# IDD_measurement.net
KiCad netlist of a schematic drawn in Altium Designer
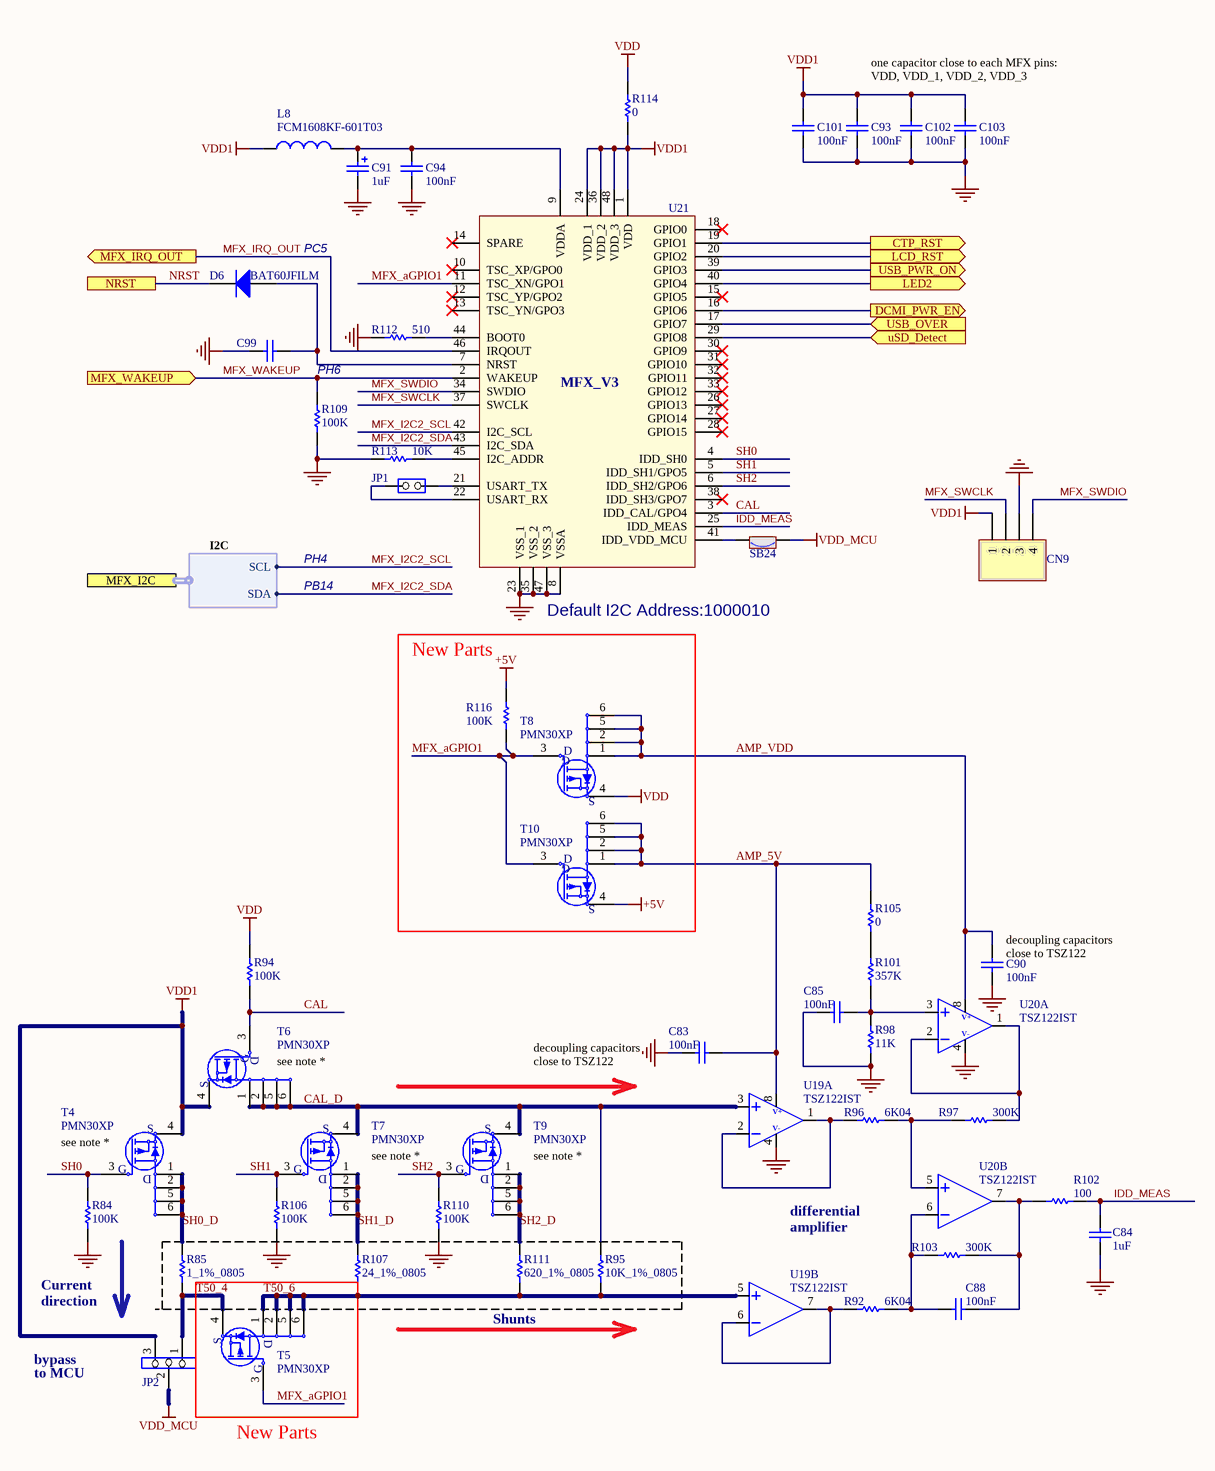
[diagram p0: IDD_measurement.SchDoc]

(export (version "E")
  (design (tool "Eeschema 10.0.6"))
  (components
    (comp (ref "C83")
      (value "100nF")
      (footprint "0603C")
      (description "Capacitor,100nF,10%,16V,X7R,0603,YAGEO")
      (fields (field (name "Comment") "CC0603KRX7R7BB104") (field (name "PUBLISHER") "Altium Limited"))
      (libsource (lib "Miscellaneous Devices") (part "Cap"))
    )
    (comp (ref "C84")
      (value "1uF")
      (footprint "0603C")
      (description "Capacitor,1uF,0603,16V,10%,X5R,YAGEO")
      (fields (field (name "Comment") "CC0603KRX5R7BB105") (field (name "PUBLISHER") "Altium Limited"))
      (libsource (lib "Miscellaneous Devices") (part "Cap"))
    )
    (comp (ref "C85")
      (value "100nF")
      (footprint "0603C")
      (description "Capacitor,100nF,10%,16V,X7R,0603,YAGEO")
      (fields (field (name "Comment") "CC0603KRX7R7BB104") (field (name "PUBLISHER") "Altium Limited"))
      (libsource (lib "Miscellaneous Devices") (part "Cap"))
    )
    (comp (ref "C88")
      (value "100nF")
      (footprint "0603C")
      (description "Capacitor,100nF,10%,16V,X7R,0603,YAGEO")
      (fields (field (name "Comment") "CC0603KRX7R7BB104") (field (name "PUBLISHER") "Altium Limited"))
      (libsource (lib "Miscellaneous Devices") (part "Cap"))
    )
    (comp (ref "C90")
      (value "100nF")
      (footprint "0603C")
      (description "Capacitor,100nF,10%,16V,X7R,0603,YAGEO")
      (fields (field (name "Comment") "CC0603KRX7R7BB104") (field (name "PUBLISHER") "Altium Limited"))
      (libsource (lib "Miscellaneous Devices") (part "Cap"))
    )
    (comp (ref "C91")
      (value "1uF")
      (footprint "TAN-A")
      (description "Tan Capacitor,1uF,10%,16V,Tan-A,TAJA105K016R")
      (fields (field (name "Comment") "TAJA105K016R") (field (name "PUBLISHER") "Altium Limited"))
      (libsource (lib "Miscellaneous Devices") (part "Cap Pol1"))
    )
    (comp (ref "C93")
      (value "100nF")
      (footprint "0603C")
      (description "Capacitor,100nF,10%,16V,X7R,0603,YAGEO")
      (fields (field (name "Comment") "CC0603KRX7R7BB104") (field (name "PUBLISHER") "Altium Limited"))
      (libsource (lib "Miscellaneous Devices") (part "Cap"))
    )
    (comp (ref "C94")
      (value "100nF")
      (footprint "0603C")
      (description "Capacitor,100nF,10%,16V,X7R,0603,YAGEO")
      (fields (field (name "Comment") "CC0603KRX7R7BB104") (field (name "PUBLISHER") "Altium Limited"))
      (libsource (lib "Miscellaneous Devices") (part "Cap"))
    )
    (comp (ref "C99")
      (value "~")
      (footprint "0603C")
      (description "Capacitor,100nF,10%,16V,X7R,0603,YAGEO")
      (fields (field (name "PUBLISHER") "Altium Limited"))
      (libsource (lib "Miscellaneous Devices") (part "Cap"))
    )
    (comp (ref "C101")
      (value "100nF")
      (footprint "0603C")
      (description "Capacitor,100nF,10%,16V,X7R,0603,YAGEO")
      (fields (field (name "Comment") "CC0603KRX7R7BB104") (field (name "PUBLISHER") "Altium Limited"))
      (libsource (lib "Miscellaneous Devices") (part "Cap"))
    )
    (comp (ref "C102")
      (value "100nF")
      (footprint "0603C")
      (description "Capacitor,100nF,10%,16V,X7R,0603,YAGEO")
      (fields (field (name "Comment") "CC0603KRX7R7BB104") (field (name "PUBLISHER") "Altium Limited"))
      (libsource (lib "Miscellaneous Devices") (part "Cap"))
    )
    (comp (ref "C103")
      (value "100nF")
      (footprint "0603C")
      (description "Capacitor,100nF,10%,16V,X7R,0603,YAGEO")
      (fields (field (name "Comment") "CC0603KRX7R7BB104") (field (name "PUBLISHER") "Altium Limited"))
      (libsource (lib "Miscellaneous Devices") (part "Cap"))
    )
    (comp (ref "CN9")
      (value "~")
      (footprint "HDR_1X4_2R54")
      (description "Header, 4-Pin")
      (fields (field (name "PUBLISHER") "Altium Limited"))
      (libsource (lib "MCD_TOOLS_CONNECTOR") (part "Header 4"))
    )
    (comp (ref "D6")
      (value "BAT60JFILM")
      (footprint "SOD-323")
      (fields (field (name "PROVIDED") "STM"))
      (libsource (lib "MCD_TOOLS") (part "BAT60JFILM"))
    )
    (comp (ref "JP1")
      (value "~")
      (footprint "SIP2")
      (description "2 PIN Jumper")
      (libsource (lib "*") (part "JP2"))
    )
    (comp (ref "JP2")
      (value "3 PIN Jumper")
      (footprint "SIP3")
      (description "Jumper 3 pins")
      (libsource (lib "MCD_TOOLS") (part "Jumper3"))
    )
    (comp (ref "L8")
      (value "FCM1608KF-601T03")
      (footprint "0603L")
      (description "Bead,600R,350mA,0603,FCM1608KF-601T03,Tai-tech")
      (libsource (lib "MCD_TOOLS") (part "BEAD_600R_350MA_0603"))
    )
    (comp (ref "R84")
      (value "100K")
      (footprint "0603R")
      (description "Resistor,100K,0603,1%,YAGEO")
      (fields (field (name "Comment") "RC0603FR-07100KL") (field (name "PUBLISHER") "Altium Limited"))
      (libsource (lib "Miscellaneous Devices") (part "res1"))
    )
    (comp (ref "R85")
      (value "1_1%_0805")
      (footprint "0805R")
      (description "Resistor,1,0805,1%,YAGEO")
      (libsource (lib "MCD_TOOLS") (part "Res_1_1%_0805"))
    )
    (comp (ref "R92")
      (value "6K04")
      (footprint "0603R")
      (description "Resistor,6.04K,0603,1%,YAGEO")
      (fields (field (name "Comment") "RC0603FR-076K04L") (field (name "PUBLISHER") "Altium Limited"))
      (libsource (lib "Miscellaneous Devices") (part "res1"))
    )
    (comp (ref "R94")
      (value "100K")
      (footprint "0603R")
      (description "Resistor,100K,0603,1%,YAGEO")
      (fields (field (name "Comment") "RC0603FR-07100KL") (field (name "PUBLISHER") "Altium Limited"))
      (libsource (lib "Miscellaneous Devices") (part "res1"))
    )
    (comp (ref "R95")
      (value "10K_1%_0805")
      (footprint "0805R")
      (description "Resistor,10K,0805,1%,YAGEO")
      (libsource (lib "MCD_TOOLS") (part "Res_10K_1%_0805"))
    )
    (comp (ref "R96")
      (value "6K04")
      (footprint "0603R")
      (description "Resistor,6.04K,0603,1%,YAGEO")
      (fields (field (name "Comment") "RC0603FR-076K04L") (field (name "PUBLISHER") "Altium Limited"))
      (libsource (lib "Miscellaneous Devices") (part "res1"))
    )
    (comp (ref "R97")
      (value "300K")
      (footprint "0603R")
      (description "Resistor,300K,0603,1%,YAGEO")
      (fields (field (name "Comment") "RC0603FR-07300KL") (field (name "PUBLISHER") "Altium Limited"))
      (libsource (lib "Miscellaneous Devices") (part "res1"))
    )
    (comp (ref "R98")
      (value "11K")
      (footprint "0603R")
      (description "Resistor,11K,0603,1%,YAGEO")
      (fields (field (name "Comment") "RC0603FR-0711KL") (field (name "PUBLISHER") "Altium Limited"))
      (libsource (lib "Miscellaneous Devices") (part "res1"))
    )
    (comp (ref "R101")
      (value "357K")
      (footprint "0603R")
      (description "Resistor,357K,0603,1%,YAGEO")
      (fields (field (name "Comment") "RC0603FR-07357KL") (field (name "PUBLISHER") "Altium Limited"))
      (libsource (lib "Miscellaneous Devices") (part "res1"))
    )
    (comp (ref "R102")
      (value "100")
      (footprint "0603R")
      (description "Resistor, 100 ,0603,1%,YAGEO")
      (fields (field (name "Comment") "RC0603JR-07100RL") (field (name "PUBLISHER") "Altium Limited"))
      (libsource (lib "Miscellaneous Devices") (part "res1"))
    )
    (comp (ref "R103")
      (value "300K")
      (footprint "0603R")
      (description "Resistor,300K,0603,1%,YAGEO")
      (fields (field (name "Comment") "RC0603FR-07300KL") (field (name "PUBLISHER") "Altium Limited"))
      (libsource (lib "Miscellaneous Devices") (part "res1"))
    )
    (comp (ref "R105")
      (value "0")
      (footprint "0603R")
      (description "Resistor, 0 ,0603,1%,YAGEO")
      (fields (field (name "Comment") "RC0603JR-070RL") (field (name "PUBLISHER") "Altium Limited"))
      (libsource (lib "Miscellaneous Devices") (part "res1"))
    )
    (comp (ref "R106")
      (value "100K")
      (footprint "0603R")
      (description "Resistor,100K,0603,1%,YAGEO")
      (fields (field (name "Comment") "RC0603FR-07100KL") (field (name "PUBLISHER") "Altium Limited"))
      (libsource (lib "Miscellaneous Devices") (part "res1"))
    )
    (comp (ref "R107")
      (value "24_1%_0805")
      (footprint "0805R")
      (description "Resistor,24,0805,1%,YAGEO")
      (libsource (lib "MCD_TOOLS") (part "Res_24_1%_0805"))
    )
    (comp (ref "R109")
      (value "100K")
      (footprint "0603R")
      (description "Resistor,100K,0603,1%,YAGEO")
      (fields (field (name "Comment") "RC0603FR-07100KL") (field (name "PUBLISHER") "Altium Limited"))
      (libsource (lib "Miscellaneous Devices") (part "res1"))
    )
    (comp (ref "R110")
      (value "100K")
      (footprint "0603R")
      (description "Resistor,100K,0603,1%,YAGEO")
      (fields (field (name "Comment") "RC0603FR-07100KL") (field (name "PUBLISHER") "Altium Limited"))
      (libsource (lib "Miscellaneous Devices") (part "res1"))
    )
    (comp (ref "R111")
      (value "620_1%_0805")
      (footprint "0805R")
      (description "Resistor,620,0805,1%,YAGEO")
      (libsource (lib "MCD_TOOLS") (part "Res_620_1%_0805"))
    )
    (comp (ref "R112")
      (value "510")
      (footprint "0603R")
      (description "Resistor,510R,0603,1%,YAGEO")
      (fields (field (name "Comment") "RC0603FR-07510RL") (field (name "PUBLISHER") "Altium Limited"))
      (libsource (lib "Miscellaneous Devices") (part "res1"))
    )
    (comp (ref "R113")
      (value "10K")
      (footprint "0603R")
      (description "Resistor,10K,0603,1%,YAGEO")
      (fields (field (name "Comment") "RC0603FR-0710KL") (field (name "PUBLISHER") "Altium Limited"))
      (libsource (lib "Miscellaneous Devices") (part "res1"))
    )
    (comp (ref "R114")
      (value "0")
      (footprint "0603R")
      (description "Resistor, 0 ,0603,1%,YAGEO")
      (fields (field (name "Comment") "RC0603JR-070RL") (field (name "PUBLISHER") "Altium Limited"))
      (libsource (lib "Miscellaneous Devices") (part "res1"))
    )
    (comp (ref "R116")
      (value "100K")
      (footprint "0603R")
      (description "Resistor,100K,0603,1%,YAGEO")
      (fields (field (name "Comment") "RC0603FR-07100KL") (field (name "PUBLISHER") "Altium Limited"))
      (libsource (lib "Miscellaneous Devices") (part "res1"))
    )
    (comp (ref "SB24")
      (value "Solder Bridge ON")
      (footprint "SB_0603")
      (libsource (lib "MCD_TOOLS") (part "SB_ON"))
    )
    (comp (ref "T4")
      (value "PMN30XP")
      (footprint "MOS_SOT23-6L")
      (description "20 V, P-channel Trench MOSFET")
      (fields (field (name "INTERNAL_PART_NUMBER") "MCD-01926") (field (name "MANUFACTURER") "NEXPERIA"))
      (libsource (lib "MCD_PARTS_database") (part "PMN30XP"))
    )
    (comp (ref "T5")
      (value "PMN30XP")
      (footprint "MOS_SOT23-6L")
      (description "20 V, P-channel Trench MOSFET")
      (fields (field (name "INTERNAL_PART_NUMBER") "MCD-01926") (field (name "MANUFACTURER") "NEXPERIA"))
      (libsource (lib "MCD_PARTS_database") (part "PMN30XP"))
    )
    (comp (ref "T6")
      (value "PMN30XP")
      (footprint "MOS_SOT23-6L")
      (description "20 V, P-channel Trench MOSFET")
      (fields (field (name "INTERNAL_PART_NUMBER") "MCD-01926") (field (name "MANUFACTURER") "NEXPERIA"))
      (libsource (lib "MCD_PARTS_database") (part "PMN30XP"))
    )
    (comp (ref "T7")
      (value "PMN30XP")
      (footprint "MOS_SOT23-6L")
      (description "20 V, P-channel Trench MOSFET")
      (fields (field (name "INTERNAL_PART_NUMBER") "MCD-01926") (field (name "MANUFACTURER") "NEXPERIA"))
      (libsource (lib "MCD_PARTS_database") (part "PMN30XP"))
    )
    (comp (ref "T8")
      (value "PMN30XP")
      (footprint "MOS_SOT23-6L")
      (description "20 V, P-channel Trench MOSFET")
      (fields (field (name "INTERNAL_PART_NUMBER") "MCD-01926") (field (name "MANUFACTURER") "NEXPERIA"))
      (libsource (lib "MCD_PARTS_database") (part "PMN30XP"))
    )
    (comp (ref "T9")
      (value "PMN30XP")
      (footprint "MOS_SOT23-6L")
      (description "20 V, P-channel Trench MOSFET")
      (fields (field (name "INTERNAL_PART_NUMBER") "MCD-01926") (field (name "MANUFACTURER") "NEXPERIA"))
      (libsource (lib "MCD_PARTS_database") (part "PMN30XP"))
    )
    (comp (ref "T10")
      (value "PMN30XP")
      (footprint "MOS_SOT23-6L")
      (description "20 V, P-channel Trench MOSFET")
      (fields (field (name "INTERNAL_PART_NUMBER") "MCD-01926") (field (name "MANUFACTURER") "NEXPERIA"))
      (libsource (lib "MCD_PARTS_database") (part "PMN30XP"))
    )
    (comp (ref "U19")
      (value "TSZ122IST")
      (footprint "miniSO8")
      (description "Very high accuracy (5 礦) zero drift 5 V dual OpAmp")
      (libsource (lib "MCD_TOOLS") (part "TSZ122IST"))
    )
    (comp (ref "U20")
      (value "TSZ122IST")
      (footprint "miniSO8")
      (description "Very high accuracy (5 礦) zero drift 5 V dual OpAmp")
      (libsource (lib "MCD_TOOLS") (part "TSZ122IST"))
    )
    (comp (ref "U21")
      (value "STM32L152CCT6")
      (footprint "LQFP48_0R5_9X9")
      (description "Multifunction expander")
      (libsource (lib "MB1167") (part "MFX"))
    )
  )
  (nets
    (net (code "2") (name "+5V") (class "Default")
      (node (ref "R116") (pin "2") (pinfunction "2_2") (pintype "passive"))
      (node (ref "T10") (pin "4") (pinfunction "S_4") (pintype "passive"))
    )
    (net (code "3") (name "/AMP_5V") (class "Default")
      (node (ref "C83") (pin "2") (pinfunction "2_2") (pintype "passive"))
      (node (ref "R105") (pin "2") (pinfunction "2_2") (pintype "passive"))
      (node (ref "T10") (pin "1") (pinfunction "S_1") (pintype "passive"))
      (node (ref "T10") (pin "2") (pinfunction "S_2") (pintype "passive"))
      (node (ref "T10") (pin "5") (pinfunction "D_5") (pintype "passive"))
      (node (ref "T10") (pin "6") (pinfunction "D_6") (pintype "passive"))
      (node (ref "U19") (pin "8") (pintype "passive"))
    )
    (net (code "4") (name "/AMP_VDD") (class "Default")
      (node (ref "C90") (pin "1") (pinfunction "1_1") (pintype "passive"))
      (node (ref "T8") (pin "1") (pinfunction "S_1") (pintype "passive"))
      (node (ref "T8") (pin "2") (pinfunction "S_2") (pintype "passive"))
      (node (ref "T8") (pin "5") (pinfunction "D_5") (pintype "passive"))
      (node (ref "T8") (pin "6") (pinfunction "D_6") (pintype "passive"))
      (node (ref "U20") (pin "8") (pintype "passive"))
    )
    (net (code "5") (name "/CAL") (class "Default")
      (node (ref "R94") (pin "1") (pinfunction "1_1") (pintype "passive"))
      (node (ref "T6") (pin "3") (pinfunction "G_3") (pintype "passive"))
      (node (ref "U21") (pin "3") (pinfunction "IDD_CAL/GPO4_3") (pintype "passive"))
    )
    (net (code "6") (name "/CAL_D") (class "Default")
      (node (ref "R95") (pin "2") (pinfunction "2_2") (pintype "passive"))
      (node (ref "T6") (pin "1") (pinfunction "S_1") (pintype "passive"))
      (node (ref "T6") (pin "2") (pinfunction "S_2") (pintype "passive"))
      (node (ref "T6") (pin "5") (pinfunction "D_5") (pintype "passive"))
      (node (ref "T6") (pin "6") (pinfunction "D_6") (pintype "passive"))
      (node (ref "T7") (pin "4") (pinfunction "S_4") (pintype "passive"))
      (node (ref "T9") (pin "4") (pinfunction "S_4") (pintype "passive"))
      (node (ref "U19") (pin "3") (pintype "passive"))
    )
    (net (code "7") (name "/CTP_RST") (class "Default")
      (node (ref "U21") (pin "19") (pinfunction "GPIO1_19") (pintype "passive"))
    )
    (net (code "8") (name "/DCMI_PWR_EN") (class "Default")
      (node (ref "U21") (pin "16") (pinfunction "GPIO6_16") (pintype "passive"))
    )
    (net (code "9") (name "/IDD_MEAS") (class "Default")
      (node (ref "C84") (pin "1") (pinfunction "1_1") (pintype "passive"))
      (node (ref "R102") (pin "1") (pinfunction "1_1") (pintype "passive"))
      (node (ref "U21") (pin "25") (pinfunction "IDD_MEAS_25") (pintype "passive"))
    )
    (net (code "10") (name "/LCD_RST") (class "Default")
      (node (ref "U21") (pin "20") (pinfunction "GPIO2_20") (pintype "passive"))
    )
    (net (code "11") (name "/LED2") (class "Default")
      (node (ref "U21") (pin "40") (pinfunction "GPIO4_40") (pintype "passive"))
    )
    (net (code "12") (name "/MFX_I2C2_SCL") (class "Default")
      (node (ref "U21") (pin "42") (pinfunction "I2C_SCL_42") (pintype "passive"))
    )
    (net (code "13") (name "/MFX_I2C2_SDA") (class "Default")
      (node (ref "U21") (pin "43") (pinfunction "I2C_SDA_43") (pintype "passive"))
    )
    (net (code "14") (name "/MFX_IRQ_OUT") (class "Default")
      (node (ref "U21") (pin "46") (pinfunction "IRQOUT_46") (pintype "passive"))
    )
    (net (code "15") (name "/MFX_SWCLK") (class "Default")
      (node (ref "CN9") (pin "2") (pinfunction "2_2") (pintype "passive"))
      (node (ref "U21") (pin "37") (pinfunction "SWCLK_37") (pintype "passive"))
    )
    (net (code "16") (name "/MFX_SWDIO") (class "Default")
      (node (ref "CN9") (pin "4") (pinfunction "4_4") (pintype "passive"))
      (node (ref "U21") (pin "34") (pinfunction "SWDIO_34") (pintype "passive"))
    )
    (net (code "17") (name "/MFX_WAKEUP") (class "Default")
      (node (ref "R109") (pin "2") (pinfunction "2_2") (pintype "passive"))
      (node (ref "U21") (pin "2") (pinfunction "WAKEUP_2") (pintype "passive"))
    )
    (net (code "18") (name "/MFX_aGPIO1") (class "Default")
      (node (ref "R116") (pin "1") (pinfunction "1_1") (pintype "passive"))
      (node (ref "T10") (pin "3") (pinfunction "G_3") (pintype "passive"))
      (node (ref "T5") (pin "3") (pinfunction "G_3") (pintype "passive"))
      (node (ref "T8") (pin "3") (pinfunction "G_3") (pintype "passive"))
      (node (ref "U21") (pin "11") (pinfunction "TSC_XN/GPO1_11") (pintype "passive"))
    )
    (net (code "19") (name "/NRST") (class "Default")
      (node (ref "D6") (pin "2") (pinfunction "K_2") (pintype "passive"))
    )
    (net (code "20") (name "/SH0") (class "Default")
      (node (ref "R84") (pin "2") (pinfunction "2_2") (pintype "passive"))
      (node (ref "T4") (pin "3") (pinfunction "G_3") (pintype "passive"))
      (node (ref "U21") (pin "4") (pinfunction "IDD_SH0_4") (pintype "passive"))
    )
    (net (code "21") (name "/SH0_D") (class "Default")
      (node (ref "R85") (pin "2") (pinfunction "2_2") (pintype "passive"))
      (node (ref "T4") (pin "1") (pinfunction "S_1") (pintype "passive"))
      (node (ref "T4") (pin "2") (pinfunction "S_2") (pintype "passive"))
      (node (ref "T4") (pin "5") (pinfunction "D_5") (pintype "passive"))
      (node (ref "T4") (pin "6") (pinfunction "D_6") (pintype "passive"))
    )
    (net (code "22") (name "/SH1") (class "Default")
      (node (ref "R106") (pin "2") (pinfunction "2_2") (pintype "passive"))
      (node (ref "T7") (pin "3") (pinfunction "G_3") (pintype "passive"))
      (node (ref "U21") (pin "5") (pinfunction "IDD_SH1/GPO5_5") (pintype "passive"))
    )
    (net (code "23") (name "/SH1_D") (class "Default")
      (node (ref "R107") (pin "2") (pinfunction "2_2") (pintype "passive"))
      (node (ref "T7") (pin "1") (pinfunction "S_1") (pintype "passive"))
      (node (ref "T7") (pin "2") (pinfunction "S_2") (pintype "passive"))
      (node (ref "T7") (pin "5") (pinfunction "D_5") (pintype "passive"))
      (node (ref "T7") (pin "6") (pinfunction "D_6") (pintype "passive"))
    )
    (net (code "24") (name "/SH2") (class "Default")
      (node (ref "R110") (pin "2") (pinfunction "2_2") (pintype "passive"))
      (node (ref "T9") (pin "3") (pinfunction "G_3") (pintype "passive"))
      (node (ref "U21") (pin "6") (pinfunction "IDD_SH2/GPO6_6") (pintype "passive"))
    )
    (net (code "25") (name "/SH2_D") (class "Default")
      (node (ref "R111") (pin "2") (pinfunction "2_2") (pintype "passive"))
      (node (ref "T9") (pin "1") (pinfunction "S_1") (pintype "passive"))
      (node (ref "T9") (pin "2") (pinfunction "S_2") (pintype "passive"))
      (node (ref "T9") (pin "5") (pinfunction "D_5") (pintype "passive"))
      (node (ref "T9") (pin "6") (pinfunction "D_6") (pintype "passive"))
    )
    (net (code "26") (name "/T50_4") (class "Default")
      (node (ref "JP2") (pin "1") (pintype "passive"))
      (node (ref "R85") (pin "1") (pinfunction "1_1") (pintype "passive"))
      (node (ref "T5") (pin "4") (pinfunction "S_4") (pintype "passive"))
    )
    (net (code "27") (name "/T50_6") (class "Default")
      (node (ref "R107") (pin "1") (pinfunction "1_1") (pintype "passive"))
      (node (ref "R111") (pin "1") (pinfunction "1_1") (pintype "passive"))
      (node (ref "R95") (pin "1") (pinfunction "1_1") (pintype "passive"))
      (node (ref "T5") (pin "1") (pinfunction "S_1") (pintype "passive"))
      (node (ref "T5") (pin "2") (pinfunction "S_2") (pintype "passive"))
      (node (ref "T5") (pin "5") (pinfunction "D_5") (pintype "passive"))
      (node (ref "T5") (pin "6") (pinfunction "D_6") (pintype "passive"))
      (node (ref "U19") (pin "5") (pintype "passive"))
    )
    (net (code "28") (name "/USB_OVER") (class "Default")
      (node (ref "U21") (pin "17") (pinfunction "GPIO7_17") (pintype "passive"))
    )
    (net (code "29") (name "/USB_PWR_ON") (class "Default")
      (node (ref "U21") (pin "39") (pinfunction "GPIO3_39") (pintype "passive"))
    )
    (net (code "30") (name "/uSD_Detect") (class "Default")
      (node (ref "U21") (pin "29") (pinfunction "GPIO8_29") (pintype "passive"))
    )
    (net (code "32") (name "GND") (class "Default")
      (node (ref "C101") (pin "2") (pinfunction "2_2") (pintype "passive"))
      (node (ref "C102") (pin "2") (pinfunction "2_2") (pintype "passive"))
      (node (ref "C103") (pin "2") (pinfunction "2_2") (pintype "passive"))
      (node (ref "C83") (pin "1") (pinfunction "1_1") (pintype "passive"))
      (node (ref "C84") (pin "2") (pinfunction "2_2") (pintype "passive"))
      (node (ref "C85") (pin "1") (pinfunction "1_1") (pintype "passive"))
      (node (ref "C90") (pin "2") (pinfunction "2_2") (pintype "passive"))
      (node (ref "C91") (pin "2") (pinfunction "2_2") (pintype "passive"))
      (node (ref "C93") (pin "2") (pinfunction "2_2") (pintype "passive"))
      (node (ref "C94") (pin "2") (pinfunction "2_2") (pintype "passive"))
      (node (ref "C99") (pin "1") (pinfunction "1_1") (pintype "passive"))
      (node (ref "CN9") (pin "3") (pinfunction "3_3") (pintype "passive"))
      (node (ref "R106") (pin "1") (pinfunction "1_1") (pintype "passive"))
      (node (ref "R109") (pin "1") (pinfunction "1_1") (pintype "passive"))
      (node (ref "R110") (pin "1") (pinfunction "1_1") (pintype "passive"))
      (node (ref "R112") (pin "2") (pinfunction "2_2") (pintype "passive"))
      (node (ref "R113") (pin "2") (pinfunction "2_2") (pintype "passive"))
      (node (ref "R84") (pin "1") (pinfunction "1_1") (pintype "passive"))
      (node (ref "R98") (pin "2") (pinfunction "2_2") (pintype "passive"))
      (node (ref "U19") (pin "4") (pintype "passive"))
      (node (ref "U20") (pin "4") (pintype "passive"))
      (node (ref "U21") (pin "23") (pinfunction "VSS_1_23") (pintype "passive"))
      (node (ref "U21") (pin "35") (pinfunction "VSS_2_35") (pintype "passive"))
      (node (ref "U21") (pin "47") (pinfunction "VSS_3_47") (pintype "passive"))
      (node (ref "U21") (pin "8") (pinfunction "VSSA_8") (pintype "passive"))
    )
    (net (code "33") (name "Net-(C85-Pad2)") (class "Default")
      (node (ref "C85") (pin "2") (pinfunction "2_2") (pintype "passive"))
      (node (ref "R101") (pin "2") (pinfunction "2_2") (pintype "passive"))
      (node (ref "R98") (pin "1") (pinfunction "1_1") (pintype "passive"))
      (node (ref "U20") (pin "3") (pintype "passive"))
    )
    (net (code "34") (name "Net-(C88-Pad1)") (class "Default")
      (node (ref "C88") (pin "1") (pinfunction "1_1") (pintype "passive"))
      (node (ref "R103") (pin "1") (pinfunction "1_1") (pintype "passive"))
      (node (ref "R92") (pin "1") (pinfunction "1_1") (pintype "passive"))
      (node (ref "U20") (pin "6") (pintype "passive"))
    )
    (net (code "35") (name "Net-(C88-Pad2)") (class "Default")
      (node (ref "C88") (pin "2") (pinfunction "2_2") (pintype "passive"))
      (node (ref "R102") (pin "2") (pinfunction "2_2") (pintype "passive"))
      (node (ref "R103") (pin "2") (pinfunction "2_2") (pintype "passive"))
      (node (ref "U20") (pin "7") (pintype "passive"))
    )
    (net (code "36") (name "Net-(D6-A)") (class "Default")
      (node (ref "C99") (pin "2") (pinfunction "2_2") (pintype "passive"))
      (node (ref "D6") (pin "1") (pinfunction "A_1") (pintype "passive"))
      (node (ref "U21") (pin "7") (pinfunction "NRST_7") (pintype "passive"))
    )
    (net (code "37") (name "Net-(JP1-COMMON)") (class "Default")
      (node (ref "JP1") (pin "1") (pinfunction "COMMON_1") (pintype "passive"))
      (node (ref "U21") (pin "22") (pinfunction "USART_RX_22") (pintype "passive"))
    )
    (net (code "38") (name "Net-(JP1-NO)") (class "Default")
      (node (ref "JP1") (pin "2") (pinfunction "NO_2") (pintype "passive"))
      (node (ref "U21") (pin "21") (pinfunction "USART_TX_21") (pintype "passive"))
    )
    (net (code "39") (name "Net-(R92-Pad2)") (class "Default")
      (node (ref "R92") (pin "2") (pinfunction "2_2") (pintype "passive"))
      (node (ref "U19") (pin "6") (pintype "passive"))
      (node (ref "U19") (pin "7") (pintype "passive"))
    )
    (net (code "40") (name "Net-(R96-Pad1)") (class "Default")
      (node (ref "R96") (pin "1") (pinfunction "1_1") (pintype "passive"))
      (node (ref "R97") (pin "1") (pinfunction "1_1") (pintype "passive"))
      (node (ref "U20") (pin "5") (pintype "passive"))
    )
    (net (code "41") (name "Net-(R96-Pad2)") (class "Default")
      (node (ref "R96") (pin "2") (pinfunction "2_2") (pintype "passive"))
      (node (ref "U19") (pin "1") (pintype "passive"))
      (node (ref "U19") (pin "2") (pintype "passive"))
    )
    (net (code "42") (name "Net-(R97-Pad2)") (class "Default")
      (node (ref "R97") (pin "2") (pinfunction "2_2") (pintype "passive"))
      (node (ref "U20") (pin "1") (pintype "passive"))
      (node (ref "U20") (pin "2") (pintype "passive"))
    )
    (net (code "43") (name "Net-(R101-Pad1)") (class "Default")
      (node (ref "R101") (pin "1") (pinfunction "1_1") (pintype "passive"))
      (node (ref "R105") (pin "1") (pinfunction "1_1") (pintype "passive"))
    )
    (net (code "44") (name "Net-(U21-BOOT0)") (class "Default")
      (node (ref "R112") (pin "1") (pinfunction "1_1") (pintype "passive"))
      (node (ref "U21") (pin "44") (pinfunction "BOOT0_44") (pintype "passive"))
    )
    (net (code "45") (name "Net-(U21-I2C_ADDR)") (class "Default")
      (node (ref "R113") (pin "1") (pinfunction "1_1") (pintype "passive"))
      (node (ref "U21") (pin "45") (pinfunction "I2C_ADDR_45") (pintype "passive"))
    )
    (net (code "46") (name "Net-(U21-IDD_VDD_MCU)") (class "Default")
      (node (ref "SB24") (pin "2") (pinfunction "2_2") (pintype "passive"))
      (node (ref "U21") (pin "41") (pinfunction "IDD_VDD_MCU_41") (pintype "passive"))
    )
    (net (code "47") (name "Net-(U21-VDDA)") (class "Default")
      (node (ref "C91") (pin "1") (pinfunction "1_1") (pintype "passive"))
      (node (ref "C94") (pin "1") (pinfunction "1_1") (pintype "passive"))
      (node (ref "L8") (pin "2") (pinfunction "2_2") (pintype "passive"))
      (node (ref "U21") (pin "9") (pinfunction "VDDA_9") (pintype "passive"))
    )
    (net (code "48") (name "VDD") (class "Default")
      (node (ref "R114") (pin "1") (pinfunction "1_1") (pintype "passive"))
      (node (ref "R94") (pin "2") (pinfunction "2_2") (pintype "passive"))
      (node (ref "T8") (pin "4") (pinfunction "S_4") (pintype "passive"))
    )
    (net (code "49") (name "VDD1") (class "Default")
      (node (ref "C101") (pin "1") (pinfunction "1_1") (pintype "passive"))
      (node (ref "C102") (pin "1") (pinfunction "1_1") (pintype "passive"))
      (node (ref "C103") (pin "1") (pinfunction "1_1") (pintype "passive"))
      (node (ref "C93") (pin "1") (pinfunction "1_1") (pintype "passive"))
      (node (ref "CN9") (pin "1") (pinfunction "1_1") (pintype "passive"))
      (node (ref "JP2") (pin "3") (pintype "passive"))
      (node (ref "L8") (pin "1") (pinfunction "1_1") (pintype "passive"))
      (node (ref "R114") (pin "2") (pinfunction "2_2") (pintype "passive"))
      (node (ref "T4") (pin "4") (pinfunction "S_4") (pintype "passive"))
      (node (ref "T6") (pin "4") (pinfunction "S_4") (pintype "passive"))
      (node (ref "U21") (pin "1") (pinfunction "VDD_1") (pintype "passive"))
      (node (ref "U21") (pin "24") (pinfunction "VDD_1_24") (pintype "passive"))
      (node (ref "U21") (pin "36") (pinfunction "VDD_2_36") (pintype "passive"))
      (node (ref "U21") (pin "48") (pinfunction "VDD_3_48") (pintype "passive"))
    )
    (net (code "50") (name "VDD_MCU") (class "Default")
      (node (ref "JP2") (pin "2") (pintype "passive"))
      (node (ref "SB24") (pin "1") (pinfunction "1_1") (pintype "passive"))
    )
    (net (code "51") (name "unconnected-(U21-GPIO0-Pad18)") (class "Default")
      (node (ref "U21") (pin "18") (pinfunction "GPIO0_18") (pintype "passive+no_connect"))
    )
    (net (code "52") (name "unconnected-(U21-GPIO5-Pad15)") (class "Default")
      (node (ref "U21") (pin "15") (pinfunction "GPIO5_15") (pintype "passive+no_connect"))
    )
    (net (code "53") (name "unconnected-(U21-GPIO9-Pad30)") (class "Default")
      (node (ref "U21") (pin "30") (pinfunction "GPIO9_30") (pintype "passive+no_connect"))
    )
    (net (code "54") (name "unconnected-(U21-GPIO10-Pad31)") (class "Default")
      (node (ref "U21") (pin "31") (pinfunction "GPIO10_31") (pintype "passive+no_connect"))
    )
    (net (code "55") (name "unconnected-(U21-GPIO11-Pad32)") (class "Default")
      (node (ref "U21") (pin "32") (pinfunction "GPIO11_32") (pintype "passive+no_connect"))
    )
    (net (code "56") (name "unconnected-(U21-GPIO12-Pad33)") (class "Default")
      (node (ref "U21") (pin "33") (pinfunction "GPIO12_33") (pintype "passive+no_connect"))
    )
    (net (code "57") (name "unconnected-(U21-GPIO13-Pad26)") (class "Default")
      (node (ref "U21") (pin "26") (pinfunction "GPIO13_26") (pintype "passive+no_connect"))
    )
    (net (code "58") (name "unconnected-(U21-GPIO14-Pad27)") (class "Default")
      (node (ref "U21") (pin "27") (pinfunction "GPIO14_27") (pintype "passive+no_connect"))
    )
    (net (code "59") (name "unconnected-(U21-GPIO15-Pad28)") (class "Default")
      (node (ref "U21") (pin "28") (pinfunction "GPIO15_28") (pintype "passive+no_connect"))
    )
    (net (code "60") (name "unconnected-(U21-IDD_SH3{slash}GPO7-Pad38)") (class "Default")
      (node (ref "U21") (pin "38") (pinfunction "IDD_SH3/GPO7_38") (pintype "passive+no_connect"))
    )
    (net (code "61") (name "unconnected-(U21-SPARE-Pad14)") (class "Default")
      (node (ref "U21") (pin "14") (pinfunction "SPARE_14") (pintype "passive+no_connect"))
    )
    (net (code "62") (name "unconnected-(U21-TSC_XP{slash}GPO0-Pad10)") (class "Default")
      (node (ref "U21") (pin "10") (pinfunction "TSC_XP/GPO0_10") (pintype "passive+no_connect"))
    )
    (net (code "63") (name "unconnected-(U21-TSC_YN{slash}GPO3-Pad13)") (class "Default")
      (node (ref "U21") (pin "13") (pinfunction "TSC_YN/GPO3_13") (pintype "passive+no_connect"))
    )
    (net (code "64") (name "unconnected-(U21-TSC_YP{slash}GPO2-Pad12)") (class "Default")
      (node (ref "U21") (pin "12") (pinfunction "TSC_YP/GPO2_12") (pintype "passive+no_connect"))
    )
  )
)
